# DDR_Memory.net
KiCad netlist of a schematic drawn in Altium Designer
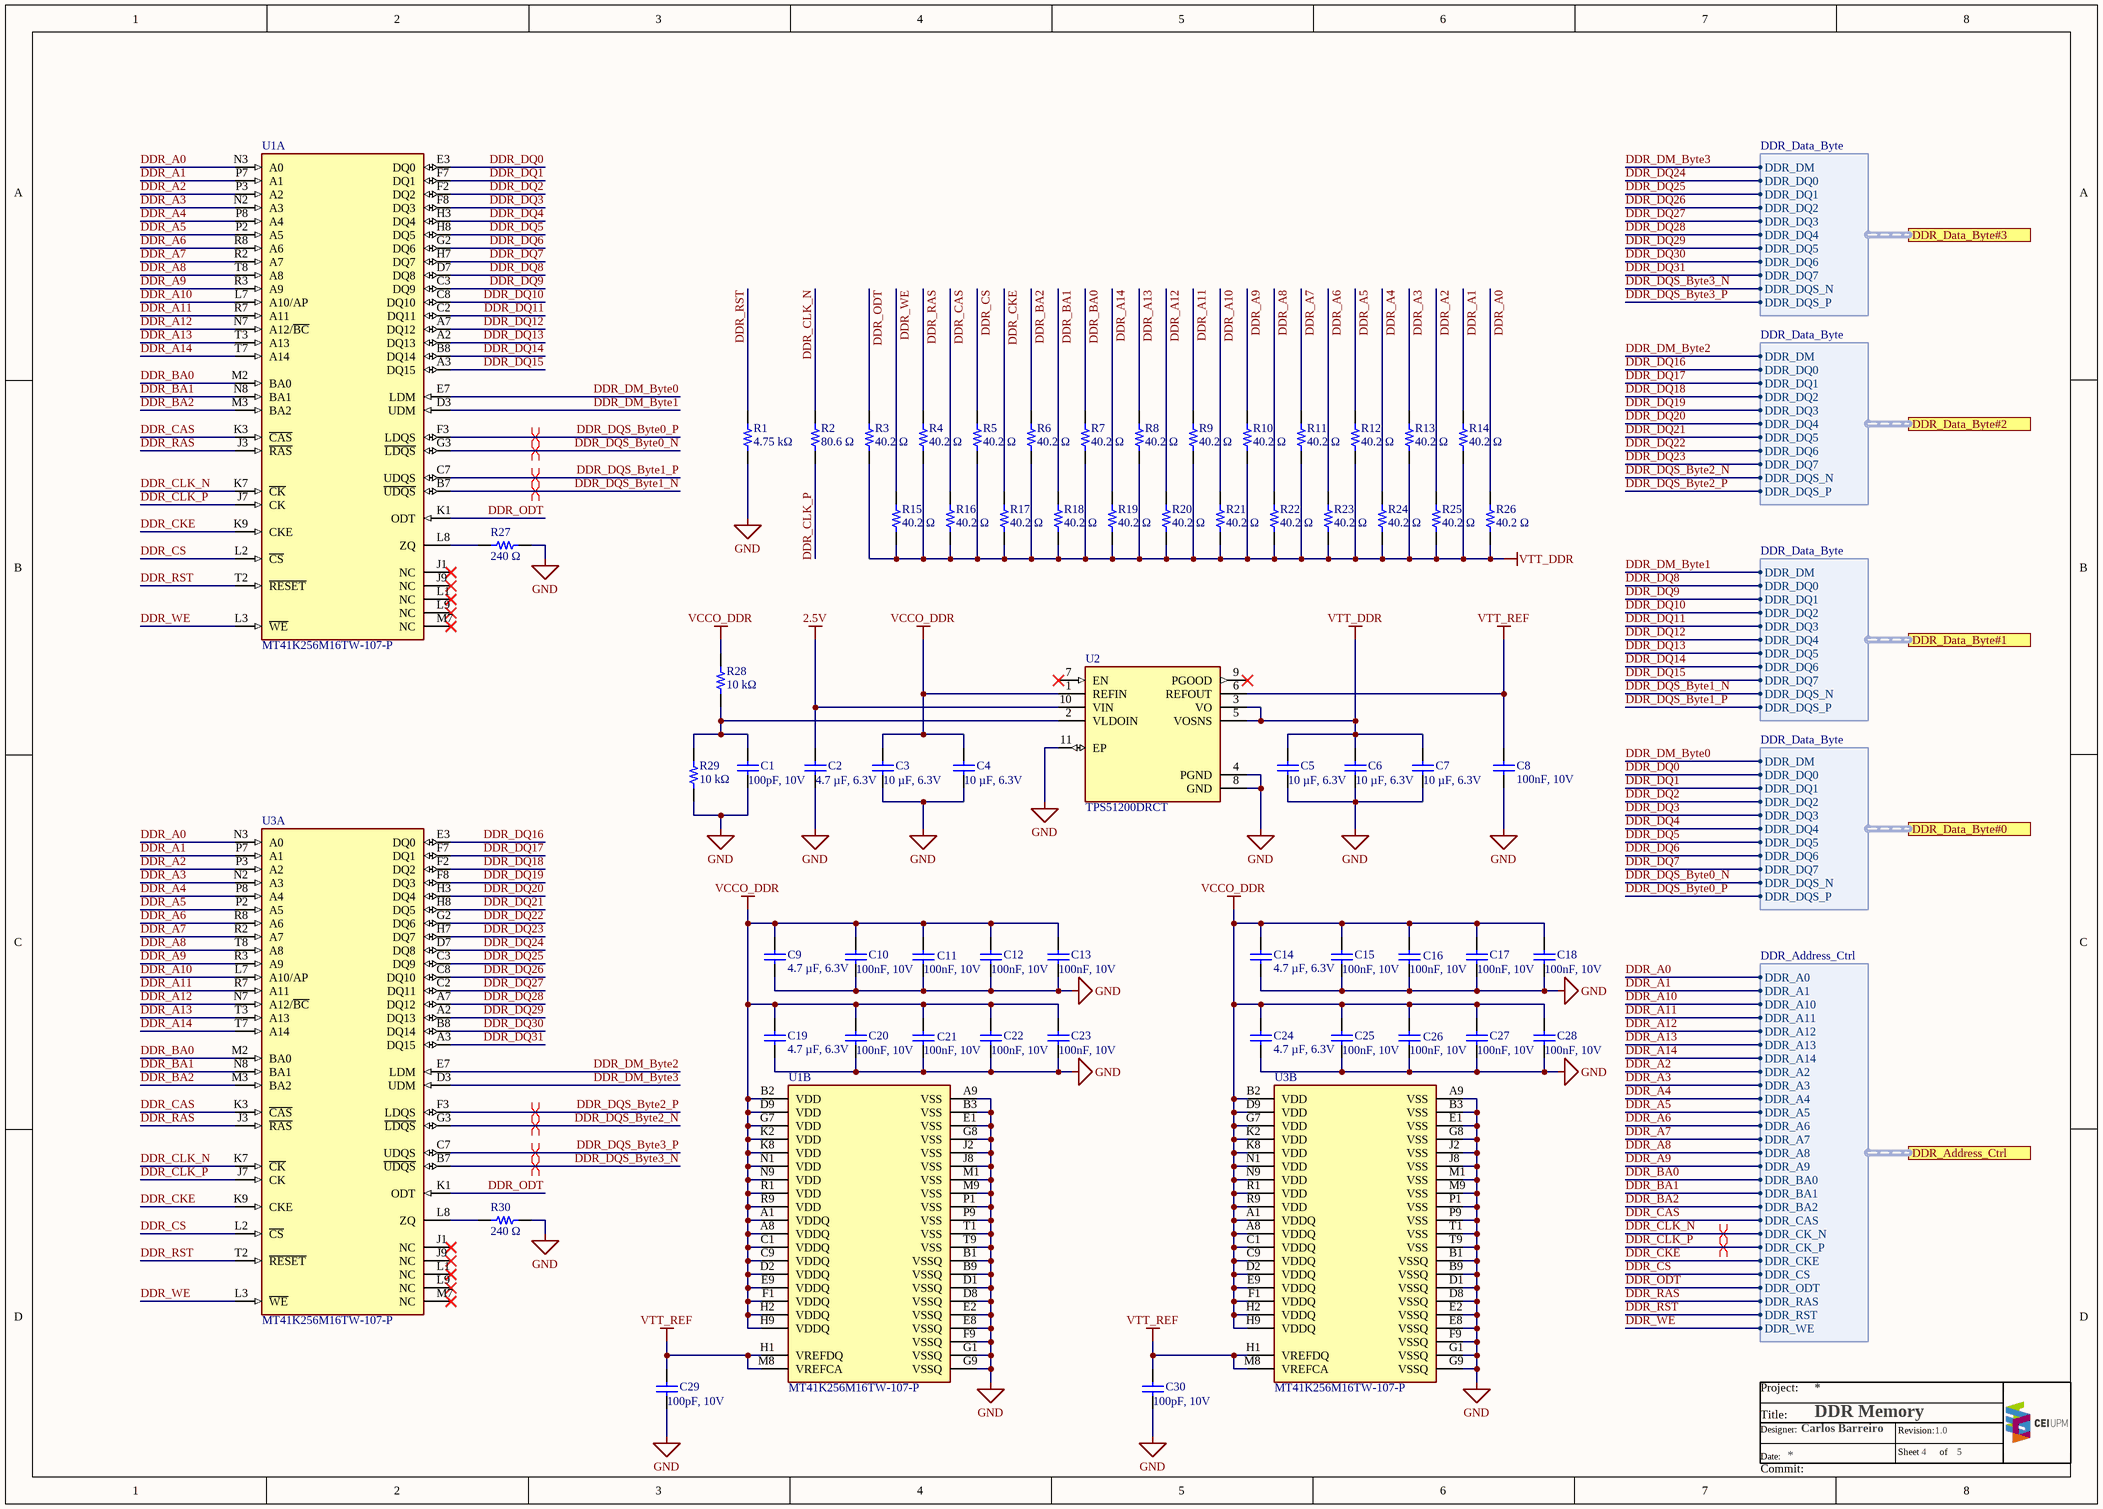
[diagram p0: DDR_Memory.SchDoc]

(export (version "E")
  (design (tool "Eeschema 10.0.6"))
  (components
    (comp (ref "C1")
      (value "100pF, 10V")
      (footprint "WURTH_WCAP-CSGP_0402")
      (description "WCAP-CSGP Multilayer Ceramic Chip Capacitor, General Purpose, size 0402, NP0, 100pF, 10V")
      (fields
        (field (name "MANUFACTURER PART NUMBER") "885012005013")
        (field (name "MANUFACTURER") "Wurth Elektronik")
      )
      (libsource (lib "SpaceVNXBaseBoard") (part "885012005013"))
    )
    (comp (ref "C2")
      (value "4.7 µF, 6.3V")
      (footprint "WURTH_WCAP-CSGP_0402")
      (description "Multilayer Ceramic Capacitors MLCC, size 0402, X5R, 4.7 µF, 6.3V")
      (fields
        (field (name "MANUFACTURER PART NUMBER") "GRM155C80J475MEAAD")
        (field (name "MANUFACTURER") "Murata")
      )
      (libsource (lib "SpaceVNXBaseBoard") (part "GRM155C80J475MEAAD"))
    )
    (comp (ref "C3")
      (value "10 µF, 6.3V")
      (footprint "WURTH_WCAP-CSGP_0402")
      (description "WCAP-CSGP Multilayer Ceramic Chip Capacitor, General Purpose, size 0402, X5R, 10uF, 6.3V")
      (fields
        (field (name "MANUFACTURER PART NUMBER") "885012105020")
        (field (name "MANUFACTURER") "Wurth Elektronik")
      )
      (libsource (lib "SpaceVNXBaseBoard") (part "885012105020"))
    )
    (comp (ref "C4")
      (value "10 µF, 6.3V")
      (footprint "WURTH_WCAP-CSGP_0402")
      (description "WCAP-CSGP Multilayer Ceramic Chip Capacitor, General Purpose, size 0402, X5R, 10uF, 6.3V")
      (fields
        (field (name "MANUFACTURER PART NUMBER") "885012105020")
        (field (name "MANUFACTURER") "Wurth Elektronik")
      )
      (libsource (lib "SpaceVNXBaseBoard") (part "885012105020"))
    )
    (comp (ref "C5")
      (value "10 µF, 6.3V")
      (footprint "WURTH_WCAP-CSGP_0402")
      (description "WCAP-CSGP Multilayer Ceramic Chip Capacitor, General Purpose, size 0402, X5R, 10uF, 6.3V")
      (fields
        (field (name "MANUFACTURER PART NUMBER") "885012105020")
        (field (name "MANUFACTURER") "Wurth Elektronik")
      )
      (libsource (lib "SpaceVNXBaseBoard") (part "885012105020"))
    )
    (comp (ref "C6")
      (value "10 µF, 6.3V")
      (footprint "WURTH_WCAP-CSGP_0402")
      (description "WCAP-CSGP Multilayer Ceramic Chip Capacitor, General Purpose, size 0402, X5R, 10uF, 6.3V")
      (fields
        (field (name "MANUFACTURER PART NUMBER") "885012105020")
        (field (name "MANUFACTURER") "Wurth Elektronik")
      )
      (libsource (lib "SpaceVNXBaseBoard") (part "885012105020"))
    )
    (comp (ref "C7")
      (value "10 µF, 6.3V")
      (footprint "WURTH_WCAP-CSGP_0402")
      (description "WCAP-CSGP Multilayer Ceramic Chip Capacitor, General Purpose, size 0402, X5R, 10uF, 6.3V")
      (fields
        (field (name "MANUFACTURER PART NUMBER") "885012105020")
        (field (name "MANUFACTURER") "Wurth Elektronik")
      )
      (libsource (lib "SpaceVNXBaseBoard") (part "885012105020"))
    )
    (comp (ref "C8")
      (value "100nF, 10V")
      (footprint "WURTH_WCAP-CSGP_0402")
      (description "WCAP-CSGP Multilayer Ceramic Chip Capacitor, General Purpose, size 0402, X7R, 100nF, 10V")
      (fields
        (field (name "MANUFACTURER PART NUMBER") "885012205018")
        (field (name "MANUFACTURER") "Wurth Elektronik")
      )
      (libsource (lib "SpaceVNXBaseBoard") (part "885012205018"))
    )
    (comp (ref "C9")
      (value "4.7 µF, 6.3V")
      (footprint "WURTH_WCAP-CSGP_0402")
      (description "Multilayer Ceramic Capacitors MLCC, size 0402, X5R, 4.7 µF, 6.3V")
      (fields
        (field (name "MANUFACTURER PART NUMBER") "GRM155C80J475MEAAD")
        (field (name "MANUFACTURER") "Murata")
      )
      (libsource (lib "SpaceVNXBaseBoard") (part "GRM155C80J475MEAAD"))
    )
    (comp (ref "C10")
      (value "100nF, 10V")
      (footprint "WURTH_WCAP-CSGP_0402")
      (description "WCAP-CSGP Multilayer Ceramic Chip Capacitor, General Purpose, size 0402, X7R, 100nF, 10V")
      (fields
        (field (name "MANUFACTURER PART NUMBER") "885012205018")
        (field (name "MANUFACTURER") "Wurth Elektronik")
      )
      (libsource (lib "SpaceVNXBaseBoard") (part "885012205018"))
    )
    (comp (ref "C11")
      (value "100nF, 10V")
      (footprint "WURTH_WCAP-CSGP_0402")
      (description "WCAP-CSGP Multilayer Ceramic Chip Capacitor, General Purpose, size 0402, X7R, 100nF, 10V")
      (fields
        (field (name "MANUFACTURER PART NUMBER") "885012205018")
        (field (name "MANUFACTURER") "Wurth Elektronik")
      )
      (libsource (lib "SpaceVNXBaseBoard") (part "885012205018"))
    )
    (comp (ref "C12")
      (value "100nF, 10V")
      (footprint "WURTH_WCAP-CSGP_0402")
      (description "WCAP-CSGP Multilayer Ceramic Chip Capacitor, General Purpose, size 0402, X7R, 100nF, 10V")
      (fields
        (field (name "MANUFACTURER PART NUMBER") "885012205018")
        (field (name "MANUFACTURER") "Wurth Elektronik")
      )
      (libsource (lib "SpaceVNXBaseBoard") (part "885012205018"))
    )
    (comp (ref "C13")
      (value "100nF, 10V")
      (footprint "WURTH_WCAP-CSGP_0402")
      (description "WCAP-CSGP Multilayer Ceramic Chip Capacitor, General Purpose, size 0402, X7R, 100nF, 10V")
      (fields
        (field (name "MANUFACTURER PART NUMBER") "885012205018")
        (field (name "MANUFACTURER") "Wurth Elektronik")
      )
      (libsource (lib "SpaceVNXBaseBoard") (part "885012205018"))
    )
    (comp (ref "C14")
      (value "4.7 µF, 6.3V")
      (footprint "WURTH_WCAP-CSGP_0402")
      (description "Multilayer Ceramic Capacitors MLCC, size 0402, X5R, 4.7 µF, 6.3V")
      (fields
        (field (name "MANUFACTURER PART NUMBER") "GRM155C80J475MEAAD")
        (field (name "MANUFACTURER") "Murata")
      )
      (libsource (lib "SpaceVNXBaseBoard") (part "GRM155C80J475MEAAD"))
    )
    (comp (ref "C15")
      (value "100nF, 10V")
      (footprint "WURTH_WCAP-CSGP_0402")
      (description "WCAP-CSGP Multilayer Ceramic Chip Capacitor, General Purpose, size 0402, X7R, 100nF, 10V")
      (fields
        (field (name "MANUFACTURER PART NUMBER") "885012205018")
        (field (name "MANUFACTURER") "Wurth Elektronik")
      )
      (libsource (lib "SpaceVNXBaseBoard") (part "885012205018"))
    )
    (comp (ref "C16")
      (value "100nF, 10V")
      (footprint "WURTH_WCAP-CSGP_0402")
      (description "WCAP-CSGP Multilayer Ceramic Chip Capacitor, General Purpose, size 0402, X7R, 100nF, 10V")
      (fields
        (field (name "MANUFACTURER PART NUMBER") "885012205018")
        (field (name "MANUFACTURER") "Wurth Elektronik")
      )
      (libsource (lib "SpaceVNXBaseBoard") (part "885012205018"))
    )
    (comp (ref "C17")
      (value "100nF, 10V")
      (footprint "WURTH_WCAP-CSGP_0402")
      (description "WCAP-CSGP Multilayer Ceramic Chip Capacitor, General Purpose, size 0402, X7R, 100nF, 10V")
      (fields
        (field (name "MANUFACTURER PART NUMBER") "885012205018")
        (field (name "MANUFACTURER") "Wurth Elektronik")
      )
      (libsource (lib "SpaceVNXBaseBoard") (part "885012205018"))
    )
    (comp (ref "C18")
      (value "100nF, 10V")
      (footprint "WURTH_WCAP-CSGP_0402")
      (description "WCAP-CSGP Multilayer Ceramic Chip Capacitor, General Purpose, size 0402, X7R, 100nF, 10V")
      (fields
        (field (name "MANUFACTURER PART NUMBER") "885012205018")
        (field (name "MANUFACTURER") "Wurth Elektronik")
      )
      (libsource (lib "SpaceVNXBaseBoard") (part "885012205018"))
    )
    (comp (ref "C19")
      (value "4.7 µF, 6.3V")
      (footprint "WURTH_WCAP-CSGP_0402")
      (description "Multilayer Ceramic Capacitors MLCC, size 0402, X5R, 4.7 µF, 6.3V")
      (fields
        (field (name "MANUFACTURER PART NUMBER") "GRM155C80J475MEAAD")
        (field (name "MANUFACTURER") "Murata")
      )
      (libsource (lib "SpaceVNXBaseBoard") (part "GRM155C80J475MEAAD"))
    )
    (comp (ref "C20")
      (value "100nF, 10V")
      (footprint "WURTH_WCAP-CSGP_0402")
      (description "WCAP-CSGP Multilayer Ceramic Chip Capacitor, General Purpose, size 0402, X7R, 100nF, 10V")
      (fields
        (field (name "MANUFACTURER PART NUMBER") "885012205018")
        (field (name "MANUFACTURER") "Wurth Elektronik")
      )
      (libsource (lib "SpaceVNXBaseBoard") (part "885012205018"))
    )
    (comp (ref "C21")
      (value "100nF, 10V")
      (footprint "WURTH_WCAP-CSGP_0402")
      (description "WCAP-CSGP Multilayer Ceramic Chip Capacitor, General Purpose, size 0402, X7R, 100nF, 10V")
      (fields
        (field (name "MANUFACTURER PART NUMBER") "885012205018")
        (field (name "MANUFACTURER") "Wurth Elektronik")
      )
      (libsource (lib "SpaceVNXBaseBoard") (part "885012205018"))
    )
    (comp (ref "C22")
      (value "100nF, 10V")
      (footprint "WURTH_WCAP-CSGP_0402")
      (description "WCAP-CSGP Multilayer Ceramic Chip Capacitor, General Purpose, size 0402, X7R, 100nF, 10V")
      (fields
        (field (name "MANUFACTURER PART NUMBER") "885012205018")
        (field (name "MANUFACTURER") "Wurth Elektronik")
      )
      (libsource (lib "SpaceVNXBaseBoard") (part "885012205018"))
    )
    (comp (ref "C23")
      (value "100nF, 10V")
      (footprint "WURTH_WCAP-CSGP_0402")
      (description "WCAP-CSGP Multilayer Ceramic Chip Capacitor, General Purpose, size 0402, X7R, 100nF, 10V")
      (fields
        (field (name "MANUFACTURER PART NUMBER") "885012205018")
        (field (name "MANUFACTURER") "Wurth Elektronik")
      )
      (libsource (lib "SpaceVNXBaseBoard") (part "885012205018"))
    )
    (comp (ref "C24")
      (value "4.7 µF, 6.3V")
      (footprint "WURTH_WCAP-CSGP_0402")
      (description "Multilayer Ceramic Capacitors MLCC, size 0402, X5R, 4.7 µF, 6.3V")
      (fields
        (field (name "MANUFACTURER PART NUMBER") "GRM155C80J475MEAAD")
        (field (name "MANUFACTURER") "Murata")
      )
      (libsource (lib "SpaceVNXBaseBoard") (part "GRM155C80J475MEAAD"))
    )
    (comp (ref "C25")
      (value "100nF, 10V")
      (footprint "WURTH_WCAP-CSGP_0402")
      (description "WCAP-CSGP Multilayer Ceramic Chip Capacitor, General Purpose, size 0402, X7R, 100nF, 10V")
      (fields
        (field (name "MANUFACTURER PART NUMBER") "885012205018")
        (field (name "MANUFACTURER") "Wurth Elektronik")
      )
      (libsource (lib "SpaceVNXBaseBoard") (part "885012205018"))
    )
    (comp (ref "C26")
      (value "100nF, 10V")
      (footprint "WURTH_WCAP-CSGP_0402")
      (description "WCAP-CSGP Multilayer Ceramic Chip Capacitor, General Purpose, size 0402, X7R, 100nF, 10V")
      (fields
        (field (name "MANUFACTURER PART NUMBER") "885012205018")
        (field (name "MANUFACTURER") "Wurth Elektronik")
      )
      (libsource (lib "SpaceVNXBaseBoard") (part "885012205018"))
    )
    (comp (ref "C27")
      (value "100nF, 10V")
      (footprint "WURTH_WCAP-CSGP_0402")
      (description "WCAP-CSGP Multilayer Ceramic Chip Capacitor, General Purpose, size 0402, X7R, 100nF, 10V")
      (fields
        (field (name "MANUFACTURER PART NUMBER") "885012205018")
        (field (name "MANUFACTURER") "Wurth Elektronik")
      )
      (libsource (lib "SpaceVNXBaseBoard") (part "885012205018"))
    )
    (comp (ref "C28")
      (value "100nF, 10V")
      (footprint "WURTH_WCAP-CSGP_0402")
      (description "WCAP-CSGP Multilayer Ceramic Chip Capacitor, General Purpose, size 0402, X7R, 100nF, 10V")
      (fields
        (field (name "MANUFACTURER PART NUMBER") "885012205018")
        (field (name "MANUFACTURER") "Wurth Elektronik")
      )
      (libsource (lib "SpaceVNXBaseBoard") (part "885012205018"))
    )
    (comp (ref "C29")
      (value "100pF, 10V")
      (footprint "WURTH_WCAP-CSGP_0402")
      (description "WCAP-CSGP Multilayer Ceramic Chip Capacitor, General Purpose, size 0402, NP0, 100pF, 10V")
      (fields
        (field (name "MANUFACTURER PART NUMBER") "885012005013")
        (field (name "MANUFACTURER") "Wurth Elektronik")
      )
      (libsource (lib "SpaceVNXBaseBoard") (part "885012005013"))
    )
    (comp (ref "C30")
      (value "100pF, 10V")
      (footprint "WURTH_WCAP-CSGP_0402")
      (description "WCAP-CSGP Multilayer Ceramic Chip Capacitor, General Purpose, size 0402, NP0, 100pF, 10V")
      (fields
        (field (name "MANUFACTURER PART NUMBER") "885012005013")
        (field (name "MANUFACTURER") "Wurth Elektronik")
      )
      (libsource (lib "SpaceVNXBaseBoard") (part "885012005013"))
    )
    (comp (ref "R1")
      (value "4.75 kΩ")
      (footprint "PANASONIC_ERJ2G_0402")
      (description "General Purpose Thick Film Chip Resistors")
      (fields (field (name "MANUFACTURER") "Panasonic"))
      (libsource (lib "SpaceVNXBaseBoard") (part "ERJ2RKF4751X"))
    )
    (comp (ref "R2")
      (value "80.6 Ω")
      (footprint "PANASONIC_ERJ2G_0402")
      (description "General Purpose Thick Film Chip Resistors")
      (fields (field (name "MANUFACTURER") "Panasonic"))
      (libsource (lib "SpaceVNXBaseBoard") (part "ERJ2RKF80R6X"))
    )
    (comp (ref "R3")
      (value "40.2 Ω")
      (footprint "PANASONIC_ERJ2G_0402")
      (description "General Purpose Thick Film Chip Resistors")
      (fields (field (name "MANUFACTURER") "Panasonic"))
      (libsource (lib "SpaceVNXBaseBoard") (part "ERJ2RKF40R2X"))
    )
    (comp (ref "R4")
      (value "40.2 Ω")
      (footprint "PANASONIC_ERJ2G_0402")
      (description "General Purpose Thick Film Chip Resistors")
      (fields (field (name "MANUFACTURER") "Panasonic"))
      (libsource (lib "SpaceVNXBaseBoard") (part "ERJ2RKF40R2X"))
    )
    (comp (ref "R5")
      (value "40.2 Ω")
      (footprint "PANASONIC_ERJ2G_0402")
      (description "General Purpose Thick Film Chip Resistors")
      (fields (field (name "MANUFACTURER") "Panasonic"))
      (libsource (lib "SpaceVNXBaseBoard") (part "ERJ2RKF40R2X"))
    )
    (comp (ref "R6")
      (value "40.2 Ω")
      (footprint "PANASONIC_ERJ2G_0402")
      (description "General Purpose Thick Film Chip Resistors")
      (fields (field (name "MANUFACTURER") "Panasonic"))
      (libsource (lib "SpaceVNXBaseBoard") (part "ERJ2RKF40R2X"))
    )
    (comp (ref "R7")
      (value "40.2 Ω")
      (footprint "PANASONIC_ERJ2G_0402")
      (description "General Purpose Thick Film Chip Resistors")
      (fields (field (name "MANUFACTURER") "Panasonic"))
      (libsource (lib "SpaceVNXBaseBoard") (part "ERJ2RKF40R2X"))
    )
    (comp (ref "R8")
      (value "40.2 Ω")
      (footprint "PANASONIC_ERJ2G_0402")
      (description "General Purpose Thick Film Chip Resistors")
      (fields (field (name "MANUFACTURER") "Panasonic"))
      (libsource (lib "SpaceVNXBaseBoard") (part "ERJ2RKF40R2X"))
    )
    (comp (ref "R9")
      (value "40.2 Ω")
      (footprint "PANASONIC_ERJ2G_0402")
      (description "General Purpose Thick Film Chip Resistors")
      (fields (field (name "MANUFACTURER") "Panasonic"))
      (libsource (lib "SpaceVNXBaseBoard") (part "ERJ2RKF40R2X"))
    )
    (comp (ref "R10")
      (value "40.2 Ω")
      (footprint "PANASONIC_ERJ2G_0402")
      (description "General Purpose Thick Film Chip Resistors")
      (fields (field (name "MANUFACTURER") "Panasonic"))
      (libsource (lib "SpaceVNXBaseBoard") (part "ERJ2RKF40R2X"))
    )
    (comp (ref "R11")
      (value "40.2 Ω")
      (footprint "PANASONIC_ERJ2G_0402")
      (description "General Purpose Thick Film Chip Resistors")
      (fields (field (name "MANUFACTURER") "Panasonic"))
      (libsource (lib "SpaceVNXBaseBoard") (part "ERJ2RKF40R2X"))
    )
    (comp (ref "R12")
      (value "40.2 Ω")
      (footprint "PANASONIC_ERJ2G_0402")
      (description "General Purpose Thick Film Chip Resistors")
      (fields (field (name "MANUFACTURER") "Panasonic"))
      (libsource (lib "SpaceVNXBaseBoard") (part "ERJ2RKF40R2X"))
    )
    (comp (ref "R13")
      (value "40.2 Ω")
      (footprint "PANASONIC_ERJ2G_0402")
      (description "General Purpose Thick Film Chip Resistors")
      (fields (field (name "MANUFACTURER") "Panasonic"))
      (libsource (lib "SpaceVNXBaseBoard") (part "ERJ2RKF40R2X"))
    )
    (comp (ref "R14")
      (value "40.2 Ω")
      (footprint "PANASONIC_ERJ2G_0402")
      (description "General Purpose Thick Film Chip Resistors")
      (fields (field (name "MANUFACTURER") "Panasonic"))
      (libsource (lib "SpaceVNXBaseBoard") (part "ERJ2RKF40R2X"))
    )
    (comp (ref "R15")
      (value "40.2 Ω")
      (footprint "PANASONIC_ERJ2G_0402")
      (description "General Purpose Thick Film Chip Resistors")
      (fields (field (name "MANUFACTURER") "Panasonic"))
      (libsource (lib "SpaceVNXBaseBoard") (part "ERJ2RKF40R2X"))
    )
    (comp (ref "R16")
      (value "40.2 Ω")
      (footprint "PANASONIC_ERJ2G_0402")
      (description "General Purpose Thick Film Chip Resistors")
      (fields (field (name "MANUFACTURER") "Panasonic"))
      (libsource (lib "SpaceVNXBaseBoard") (part "ERJ2RKF40R2X"))
    )
    (comp (ref "R17")
      (value "40.2 Ω")
      (footprint "PANASONIC_ERJ2G_0402")
      (description "General Purpose Thick Film Chip Resistors")
      (fields (field (name "MANUFACTURER") "Panasonic"))
      (libsource (lib "SpaceVNXBaseBoard") (part "ERJ2RKF40R2X"))
    )
    (comp (ref "R18")
      (value "40.2 Ω")
      (footprint "PANASONIC_ERJ2G_0402")
      (description "General Purpose Thick Film Chip Resistors")
      (fields (field (name "MANUFACTURER") "Panasonic"))
      (libsource (lib "SpaceVNXBaseBoard") (part "ERJ2RKF40R2X"))
    )
    (comp (ref "R19")
      (value "40.2 Ω")
      (footprint "PANASONIC_ERJ2G_0402")
      (description "General Purpose Thick Film Chip Resistors")
      (fields (field (name "MANUFACTURER") "Panasonic"))
      (libsource (lib "SpaceVNXBaseBoard") (part "ERJ2RKF40R2X"))
    )
    (comp (ref "R20")
      (value "40.2 Ω")
      (footprint "PANASONIC_ERJ2G_0402")
      (description "General Purpose Thick Film Chip Resistors")
      (fields (field (name "MANUFACTURER") "Panasonic"))
      (libsource (lib "SpaceVNXBaseBoard") (part "ERJ2RKF40R2X"))
    )
    (comp (ref "R21")
      (value "40.2 Ω")
      (footprint "PANASONIC_ERJ2G_0402")
      (description "General Purpose Thick Film Chip Resistors")
      (fields (field (name "MANUFACTURER") "Panasonic"))
      (libsource (lib "SpaceVNXBaseBoard") (part "ERJ2RKF40R2X"))
    )
    (comp (ref "R22")
      (value "40.2 Ω")
      (footprint "PANASONIC_ERJ2G_0402")
      (description "General Purpose Thick Film Chip Resistors")
      (fields (field (name "MANUFACTURER") "Panasonic"))
      (libsource (lib "SpaceVNXBaseBoard") (part "ERJ2RKF40R2X"))
    )
    (comp (ref "R23")
      (value "40.2 Ω")
      (footprint "PANASONIC_ERJ2G_0402")
      (description "General Purpose Thick Film Chip Resistors")
      (fields (field (name "MANUFACTURER") "Panasonic"))
      (libsource (lib "SpaceVNXBaseBoard") (part "ERJ2RKF40R2X"))
    )
    (comp (ref "R24")
      (value "40.2 Ω")
      (footprint "PANASONIC_ERJ2G_0402")
      (description "General Purpose Thick Film Chip Resistors")
      (fields (field (name "MANUFACTURER") "Panasonic"))
      (libsource (lib "SpaceVNXBaseBoard") (part "ERJ2RKF40R2X"))
    )
    (comp (ref "R25")
      (value "40.2 Ω")
      (footprint "PANASONIC_ERJ2G_0402")
      (description "General Purpose Thick Film Chip Resistors")
      (fields (field (name "MANUFACTURER") "Panasonic"))
      (libsource (lib "SpaceVNXBaseBoard") (part "ERJ2RKF40R2X"))
    )
    (comp (ref "R26")
      (value "40.2 Ω")
      (footprint "PANASONIC_ERJ2G_0402")
      (description "General Purpose Thick Film Chip Resistors")
      (fields (field (name "MANUFACTURER") "Panasonic"))
      (libsource (lib "SpaceVNXBaseBoard") (part "ERJ2RKF40R2X"))
    )
    (comp (ref "R27")
      (value "240 Ω")
      (footprint "PANASONIC_ERJ2G_0402")
      (description "General Purpose Thick Film Chip Resistors")
      (fields (field (name "MANUFACTURER") "Panasonic"))
      (libsource (lib "SpaceVNXBaseBoard") (part "ERJ2GEJ241X"))
    )
    (comp (ref "R28")
      (value "10 kΩ")
      (footprint "PANASONIC_ERJ2G_0402")
      (description "General Purpose Thick Film Chip Resistors")
      (fields (field (name "MANUFACTURER") "Panasonic"))
      (libsource (lib "SpaceVNXBaseBoard") (part "ERJ2RKF1002X"))
    )
    (comp (ref "R29")
      (value "10 kΩ")
      (footprint "PANASONIC_ERJ2G_0402")
      (description "General Purpose Thick Film Chip Resistors")
      (fields (field (name "MANUFACTURER") "Panasonic"))
      (libsource (lib "SpaceVNXBaseBoard") (part "ERJ2RKF1002X"))
    )
    (comp (ref "R30")
      (value "240 Ω")
      (footprint "PANASONIC_ERJ2G_0402")
      (description "General Purpose Thick Film Chip Resistors")
      (fields (field (name "MANUFACTURER") "Panasonic"))
      (libsource (lib "SpaceVNXBaseBoard") (part "ERJ2GEJ241X"))
    )
    (comp (ref "U1")
      (value "MT41K256M16TW-107-P")
      (footprint "Micron_TW")
      (description "DDR3L SRAM 256Mb*16")
      (libsource (lib "SpaceVNXBaseBoard") (part "MT41K256M16TW-107-P"))
    )
    (comp (ref "U2")
      (value "TPS51200DRCT")
      (footprint "TEXAS_VSON10")
      (fields (field (name "MF") "Texas Instruments"))
      (libsource (lib "SpaceVNXBaseBoard") (part "TPS51200DRCT"))
    )
    (comp (ref "U3")
      (value "MT41K256M16TW-107-P")
      (footprint "Micron_TW")
      (description "DDR3L SRAM 256Mb*16")
      (libsource (lib "SpaceVNXBaseBoard") (part "MT41K256M16TW-107-P"))
    )
  )
  (nets
    (net (code "3") (name "/DDR_A0") (class "Default")
      (node (ref "R26") (pin "1") (pinfunction "1_1") (pintype "passive"))
      (node (ref "U1") (pin "N3") (pinfunction "A0_N3") (pintype "input"))
      (node (ref "U3") (pin "N3") (pinfunction "A0_N3") (pintype "input"))
    )
    (net (code "4") (name "/DDR_A1") (class "Default")
      (node (ref "R14") (pin "1") (pinfunction "1_1") (pintype "passive"))
      (node (ref "U1") (pin "P7") (pinfunction "A1_P7") (pintype "input"))
      (node (ref "U3") (pin "P7") (pinfunction "A1_P7") (pintype "input"))
    )
    (net (code "5") (name "/DDR_A2") (class "Default")
      (node (ref "R25") (pin "1") (pinfunction "1_1") (pintype "passive"))
      (node (ref "U1") (pin "P3") (pinfunction "A2_P3") (pintype "input"))
      (node (ref "U3") (pin "P3") (pinfunction "A2_P3") (pintype "input"))
    )
    (net (code "6") (name "/DDR_A3") (class "Default")
      (node (ref "R13") (pin "1") (pinfunction "1_1") (pintype "passive"))
      (node (ref "U1") (pin "N2") (pinfunction "A3_N2") (pintype "input"))
      (node (ref "U3") (pin "N2") (pinfunction "A3_N2") (pintype "input"))
    )
    (net (code "7") (name "/DDR_A4") (class "Default")
      (node (ref "R24") (pin "1") (pinfunction "1_1") (pintype "passive"))
      (node (ref "U1") (pin "P8") (pinfunction "A4_P8") (pintype "input"))
      (node (ref "U3") (pin "P8") (pinfunction "A4_P8") (pintype "input"))
    )
    (net (code "8") (name "/DDR_A5") (class "Default")
      (node (ref "R12") (pin "1") (pinfunction "1_1") (pintype "passive"))
      (node (ref "U1") (pin "P2") (pinfunction "A5_P2") (pintype "input"))
      (node (ref "U3") (pin "P2") (pinfunction "A5_P2") (pintype "input"))
    )
    (net (code "9") (name "/DDR_A6") (class "Default")
      (node (ref "R23") (pin "1") (pinfunction "1_1") (pintype "passive"))
      (node (ref "U1") (pin "R8") (pinfunction "A6_R8") (pintype "input"))
      (node (ref "U3") (pin "R8") (pinfunction "A6_R8") (pintype "input"))
    )
    (net (code "10") (name "/DDR_A7") (class "Default")
      (node (ref "R11") (pin "1") (pinfunction "1_1") (pintype "passive"))
      (node (ref "U1") (pin "R2") (pinfunction "A7_R2") (pintype "input"))
      (node (ref "U3") (pin "R2") (pinfunction "A7_R2") (pintype "input"))
    )
    (net (code "11") (name "/DDR_A8") (class "Default")
      (node (ref "R22") (pin "1") (pinfunction "1_1") (pintype "passive"))
      (node (ref "U1") (pin "T8") (pinfunction "A8_T8") (pintype "input"))
      (node (ref "U3") (pin "T8") (pinfunction "A8_T8") (pintype "input"))
    )
    (net (code "12") (name "/DDR_A9") (class "Default")
      (node (ref "R10") (pin "1") (pinfunction "1_1") (pintype "passive"))
      (node (ref "U1") (pin "R3") (pinfunction "A9_R3") (pintype "input"))
      (node (ref "U3") (pin "R3") (pinfunction "A9_R3") (pintype "input"))
    )
    (net (code "13") (name "/DDR_A10") (class "Default")
      (node (ref "R21") (pin "1") (pinfunction "1_1") (pintype "passive"))
      (node (ref "U1") (pin "L7") (pinfunction "A10/AP_L7") (pintype "input"))
      (node (ref "U3") (pin "L7") (pinfunction "A10/AP_L7") (pintype "input"))
    )
    (net (code "14") (name "/DDR_A11") (class "Default")
      (node (ref "R9") (pin "1") (pinfunction "1_1") (pintype "passive"))
      (node (ref "U1") (pin "R7") (pinfunction "A11_R7") (pintype "input"))
      (node (ref "U3") (pin "R7") (pinfunction "A11_R7") (pintype "input"))
    )
    (net (code "15") (name "/DDR_A12") (class "Default")
      (node (ref "R20") (pin "1") (pinfunction "1_1") (pintype "passive"))
      (node (ref "U1") (pin "N7") (pinfunction "A12/~{BC}_N7") (pintype "input"))
      (node (ref "U3") (pin "N7") (pinfunction "A12/~{BC}_N7") (pintype "input"))
    )
    (net (code "16") (name "/DDR_A13") (class "Default")
      (node (ref "R8") (pin "1") (pinfunction "1_1") (pintype "passive"))
      (node (ref "U1") (pin "T3") (pinfunction "A13_T3") (pintype "input"))
      (node (ref "U3") (pin "T3") (pinfunction "A13_T3") (pintype "input"))
    )
    (net (code "17") (name "/DDR_A14") (class "Default")
      (node (ref "R19") (pin "1") (pinfunction "1_1") (pintype "passive"))
      (node (ref "U1") (pin "T7") (pinfunction "A14_T7") (pintype "input"))
      (node (ref "U3") (pin "T7") (pinfunction "A14_T7") (pintype "input"))
    )
    (net (code "18") (name "/DDR_BA0") (class "Default")
      (node (ref "R7") (pin "1") (pinfunction "1_1") (pintype "passive"))
      (node (ref "U1") (pin "M2") (pinfunction "BA0_M2") (pintype "input"))
      (node (ref "U3") (pin "M2") (pinfunction "BA0_M2") (pintype "input"))
    )
    (net (code "19") (name "/DDR_BA1") (class "Default")
      (node (ref "R18") (pin "1") (pinfunction "1_1") (pintype "passive"))
      (node (ref "U1") (pin "N8") (pinfunction "BA1_N8") (pintype "input"))
      (node (ref "U3") (pin "N8") (pinfunction "BA1_N8") (pintype "input"))
    )
    (net (code "20") (name "/DDR_BA2") (class "Default")
      (node (ref "R6") (pin "1") (pinfunction "1_1") (pintype "passive"))
      (node (ref "U1") (pin "M3") (pinfunction "BA2_M3") (pintype "input"))
      (node (ref "U3") (pin "M3") (pinfunction "BA2_M3") (pintype "input"))
    )
    (net (code "21") (name "/DDR_CAS") (class "Default")
      (node (ref "R16") (pin "1") (pinfunction "1_1") (pintype "passive"))
      (node (ref "U1") (pin "K3") (pinfunction "~{CAS}_K3") (pintype "input"))
      (node (ref "U3") (pin "K3") (pinfunction "~{CAS}_K3") (pintype "input"))
    )
    (net (code "22") (name "/DDR_CKE") (class "Default")
      (node (ref "R17") (pin "1") (pinfunction "1_1") (pintype "passive"))
      (node (ref "U1") (pin "K9") (pinfunction "CKE_K9") (pintype "input"))
      (node (ref "U3") (pin "K9") (pinfunction "CKE_K9") (pintype "input"))
    )
    (net (code "23") (name "/DDR_CLK_N") (class "Default")
      (node (ref "R2") (pin "2") (pinfunction "2_2") (pintype "passive"))
      (node (ref "U1") (pin "K7") (pinfunction "~{CK}_K7") (pintype "input"))
      (node (ref "U3") (pin "K7") (pinfunction "~{CK}_K7") (pintype "input"))
    )
    (net (code "24") (name "/DDR_CLK_P") (class "Default")
      (node (ref "R2") (pin "1") (pinfunction "1_1") (pintype "passive"))
      (node (ref "U1") (pin "J7") (pinfunction "CK_J7") (pintype "input"))
      (node (ref "U3") (pin "J7") (pinfunction "CK_J7") (pintype "input"))
    )
    (net (code "25") (name "/DDR_CS") (class "Default")
      (node (ref "R5") (pin "1") (pinfunction "1_1") (pintype "passive"))
      (node (ref "U1") (pin "L2") (pinfunction "~{CS}_L2") (pintype "input"))
      (node (ref "U3") (pin "L2") (pinfunction "~{CS}_L2") (pintype "input"))
    )
    (net (code "26") (name "/DDR_DM_Byte0") (class "Default")
      (node (ref "U1") (pin "E7") (pinfunction "LDM_E7") (pintype "input"))
    )
    (net (code "27") (name "/DDR_DM_Byte1") (class "Default")
      (node (ref "U1") (pin "D3") (pinfunction "UDM_D3") (pintype "input"))
    )
    (net (code "28") (name "/DDR_DM_Byte2") (class "Default")
      (node (ref "U3") (pin "E7") (pinfunction "LDM_E7") (pintype "input"))
    )
    (net (code "29") (name "/DDR_DM_Byte3") (class "Default")
      (node (ref "U3") (pin "D3") (pinfunction "UDM_D3") (pintype "input"))
    )
    (net (code "30") (name "/DDR_DQ0") (class "Default")
      (node (ref "U1") (pin "E3") (pinfunction "DQ0_E3") (pintype "bidirectional"))
    )
    (net (code "31") (name "/DDR_DQ1") (class "Default")
      (node (ref "U1") (pin "F7") (pinfunction "DQ1_F7") (pintype "bidirectional"))
    )
    (net (code "32") (name "/DDR_DQ2") (class "Default")
      (node (ref "U1") (pin "F2") (pinfunction "DQ2_F2") (pintype "bidirectional"))
    )
    (net (code "33") (name "/DDR_DQ3") (class "Default")
      (node (ref "U1") (pin "F8") (pinfunction "DQ3_F8") (pintype "bidirectional"))
    )
    (net (code "34") (name "/DDR_DQ4") (class "Default")
      (node (ref "U1") (pin "H3") (pinfunction "DQ4_H3") (pintype "bidirectional"))
    )
    (net (code "35") (name "/DDR_DQ5") (class "Default")
      (node (ref "U1") (pin "H8") (pinfunction "DQ5_H8") (pintype "bidirectional"))
    )
    (net (code "36") (name "/DDR_DQ6") (class "Default")
      (node (ref "U1") (pin "G2") (pinfunction "DQ6_G2") (pintype "bidirectional"))
    )
    (net (code "37") (name "/DDR_DQ7") (class "Default")
      (node (ref "U1") (pin "H7") (pinfunction "DQ7_H7") (pintype "bidirectional"))
    )
    (net (code "38") (name "/DDR_DQ8") (class "Default")
      (node (ref "U1") (pin "D7") (pinfunction "DQ8_D7") (pintype "bidirectional"))
    )
    (net (code "39") (name "/DDR_DQ9") (class "Default")
      (node (ref "U1") (pin "C3") (pinfunction "DQ9_C3") (pintype "bidirectional"))
    )
    (net (code "40") (name "/DDR_DQ10") (class "Default")
      (node (ref "U1") (pin "C8") (pinfunction "DQ10_C8") (pintype "bidirectional"))
    )
    (net (code "41") (name "/DDR_DQ11") (class "Default")
      (node (ref "U1") (pin "C2") (pinfunction "DQ11_C2") (pintype "bidirectional"))
    )
    (net (code "42") (name "/DDR_DQ12") (class "Default")
      (node (ref "U1") (pin "A7") (pinfunction "DQ12_A7") (pintype "bidirectional"))
    )
    (net (code "43") (name "/DDR_DQ13") (class "Default")
      (node (ref "U1") (pin "A2") (pinfunction "DQ13_A2") (pintype "bidirectional"))
    )
    (net (code "44") (name "/DDR_DQ14") (class "Default")
      (node (ref "U1") (pin "B8") (pinfunction "DQ14_B8") (pintype "bidirectional"))
    )
    (net (code "45") (name "/DDR_DQ15") (class "Default")
      (node (ref "U1") (pin "A3") (pinfunction "DQ15_A3") (pintype "bidirectional"))
    )
    (net (code "46") (name "/DDR_DQ16") (class "Default")
      (node (ref "U3") (pin "E3") (pinfunction "DQ0_E3") (pintype "bidirectional"))
    )
    (net (code "47") (name "/DDR_DQ17") (class "Default")
      (node (ref "U3") (pin "F7") (pinfunction "DQ1_F7") (pintype "bidirectional"))
    )
    (net (code "48") (name "/DDR_DQ18") (class "Default")
      (node (ref "U3") (pin "F2") (pinfunction "DQ2_F2") (pintype "bidirectional"))
    )
    (net (code "49") (name "/DDR_DQ19") (class "Default")
      (node (ref "U3") (pin "F8") (pinfunction "DQ3_F8") (pintype "bidirectional"))
    )
    (net (code "50") (name "/DDR_DQ20") (class "Default")
      (node (ref "U3") (pin "H3") (pinfunction "DQ4_H3") (pintype "bidirectional"))
    )
    (net (code "51") (name "/DDR_DQ21") (class "Default")
      (node (ref "U3") (pin "H8") (pinfunction "DQ5_H8") (pintype "bidirectional"))
    )
    (net (code "52") (name "/DDR_DQ22") (class "Default")
      (node (ref "U3") (pin "G2") (pinfunction "DQ6_G2") (pintype "bidirectional"))
    )
    (net (code "53") (name "/DDR_DQ23") (class "Default")
      (node (ref "U3") (pin "H7") (pinfunction "DQ7_H7") (pintype "bidirectional"))
    )
    (net (code "54") (name "/DDR_DQ24") (class "Default")
      (node (ref "U3") (pin "D7") (pinfunction "DQ8_D7") (pintype "bidirectional"))
    )
    (net (code "55") (name "/DDR_DQ25") (class "Default")
      (node (ref "U3") (pin "C3") (pinfunction "DQ9_C3") (pintype "bidirectional"))
    )
    (net (code "56") (name "/DDR_DQ26") (class "Default")
      (node (ref "U3") (pin "C8") (pinfunction "DQ10_C8") (pintype "bidirectional"))
    )
    (net (code "57") (name "/DDR_DQ27") (class "Default")
      (node (ref "U3") (pin "C2") (pinfunction "DQ11_C2") (pintype "bidirectional"))
    )
    (net (code "58") (name "/DDR_DQ28") (class "Default")
      (node (ref "U3") (pin "A7") (pinfunction "DQ12_A7") (pintype "bidirectional"))
    )
    (net (code "59") (name "/DDR_DQ29") (class "Default")
      (node (ref "U3") (pin "A2") (pinfunction "DQ13_A2") (pintype "bidirectional"))
    )
    (net (code "60") (name "/DDR_DQ30") (class "Default")
      (node (ref "U3") (pin "B8") (pinfunction "DQ14_B8") (pintype "bidirectional"))
    )
    (net (code "61") (name "/DDR_DQ31") (class "Default")
      (node (ref "U3") (pin "A3") (pinfunction "DQ15_A3") (pintype "bidirectional"))
    )
    (net (code "62") (name "/DDR_DQS_Byte0_N") (class "Default")
      (node (ref "U1") (pin "G3") (pinfunction "~{LDQS}_G3") (pintype "bidirectional"))
    )
    (net (code "63") (name "/DDR_DQS_Byte0_P") (class "Default")
      (node (ref "U1") (pin "F3") (pinfunction "LDQS_F3") (pintype "bidirectional"))
    )
    (net (code "64") (name "/DDR_DQS_Byte1_N") (class "Default")
      (node (ref "U1") (pin "B7") (pinfunction "~{UDQS}_B7") (pintype "bidirectional"))
    )
    (net (code "65") (name "/DDR_DQS_Byte1_P") (class "Default")
      (node (ref "U1") (pin "C7") (pinfunction "UDQS_C7") (pintype "bidirectional"))
    )
    (net (code "66") (name "/DDR_DQS_Byte2_N") (class "Default")
      (node (ref "U3") (pin "G3") (pinfunction "~{LDQS}_G3") (pintype "bidirectional"))
    )
    (net (code "67") (name "/DDR_DQS_Byte2_P") (class "Default")
      (node (ref "U3") (pin "F3") (pinfunction "LDQS_F3") (pintype "bidirectional"))
    )
    (net (code "68") (name "/DDR_DQS_Byte3_N") (class "Default")
      (node (ref "U3") (pin "B7") (pinfunction "~{UDQS}_B7") (pintype "bidirectional"))
    )
    (net (code "69") (name "/DDR_DQS_Byte3_P") (class "Default")
      (node (ref "U3") (pin "C7") (pinfunction "UDQS_C7") (pintype "bidirectional"))
    )
    (net (code "70") (name "/DDR_ODT") (class "Default")
      (node (ref "R3") (pin "1") (pinfunction "1_1") (pintype "passive"))
      (node (ref "U1") (pin "K1") (pinfunction "ODT_K1") (pintype "input"))
      (node (ref "U3") (pin "K1") (pinfunction "ODT_K1") (pintype "input"))
    )
    (net (code "71") (name "/DDR_RAS") (class "Default")
      (node (ref "R4") (pin "1") (pinfunction "1_1") (pintype "passive"))
      (node (ref "U1") (pin "J3") (pinfunction "~{RAS}_J3") (pintype "input"))
      (node (ref "U3") (pin "J3") (pinfunction "~{RAS}_J3") (pintype "input"))
    )
    (net (code "72") (name "/DDR_RST") (class "Default")
      (node (ref "R1") (pin "1") (pinfunction "1_1") (pintype "passive"))
      (node (ref "U1") (pin "T2") (pinfunction "~{RESET}_T2") (pintype "input"))
      (node (ref "U3") (pin "T2") (pinfunction "~{RESET}_T2") (pintype "input"))
    )
    (net (code "73") (name "/DDR_WE") (class "Default")
      (node (ref "R15") (pin "1") (pinfunction "1_1") (pintype "passive"))
      (node (ref "U1") (pin "L3") (pinfunction "~{WE}_L3") (pintype "input"))
      (node (ref "U3") (pin "L3") (pinfunction "~{WE}_L3") (pintype "input"))
    )
    (net (code "76") (name "2.5V") (class "Default")
      (node (ref "C2") (pin "2") (pinfunction "2_2") (pintype "passive"))
      (node (ref "U2") (pin "10") (pinfunction "VIN_10") (pintype "passive"))
    )
    (net (code "77") (name "GND") (class "Default")
      (node (ref "C1") (pin "1") (pinfunction "1_1") (pintype "passive"))
      (node (ref "C10") (pin "1") (pinfunction "1_1") (pintype "passive"))
      (node (ref "C11") (pin "1") (pinfunction "1_1") (pintype "passive"))
      (node (ref "C12") (pin "1") (pinfunction "1_1") (pintype "passive"))
      (node (ref "C13") (pin "1") (pinfunction "1_1") (pintype "passive"))
      (node (ref "C14") (pin "1") (pinfunction "1_1") (pintype "passive"))
      (node (ref "C15") (pin "1") (pinfunction "1_1") (pintype "passive"))
      (node (ref "C16") (pin "1") (pinfunction "1_1") (pintype "passive"))
      (node (ref "C17") (pin "1") (pinfunction "1_1") (pintype "passive"))
      (node (ref "C18") (pin "1") (pinfunction "1_1") (pintype "passive"))
      (node (ref "C19") (pin "1") (pinfunction "1_1") (pintype "passive"))
      (node (ref "C2") (pin "1") (pinfunction "1_1") (pintype "passive"))
      (node (ref "C20") (pin "1") (pinfunction "1_1") (pintype "passive"))
      (node (ref "C21") (pin "1") (pinfunction "1_1") (pintype "passive"))
      (node (ref "C22") (pin "1") (pinfunction "1_1") (pintype "passive"))
      (node (ref "C23") (pin "1") (pinfunction "1_1") (pintype "passive"))
      (node (ref "C24") (pin "1") (pinfunction "1_1") (pintype "passive"))
      (node (ref "C25") (pin "1") (pinfunction "1_1") (pintype "passive"))
      (node (ref "C26") (pin "1") (pinfunction "1_1") (pintype "passive"))
      (node (ref "C27") (pin "1") (pinfunction "1_1") (pintype "passive"))
      (node (ref "C28") (pin "1") (pinfunction "1_1") (pintype "passive"))
      (node (ref "C29") (pin "1") (pinfunction "1_1") (pintype "passive"))
      (node (ref "C3") (pin "1") (pinfunction "1_1") (pintype "passive"))
      (node (ref "C30") (pin "1") (pinfunction "1_1") (pintype "passive"))
      (node (ref "C4") (pin "1") (pinfunction "1_1") (pintype "passive"))
      (node (ref "C5") (pin "1") (pinfunction "1_1") (pintype "passive"))
      (node (ref "C6") (pin "1") (pinfunction "1_1") (pintype "passive"))
      (node (ref "C7") (pin "1") (pinfunction "1_1") (pintype "passive"))
      (node (ref "C8") (pin "1") (pinfunction "1_1") (pintype "passive"))
      (node (ref "C9") (pin "1") (pinfunction "1_1") (pintype "passive"))
      (node (ref "R1") (pin "2") (pinfunction "2_2") (pintype "passive"))
      (node (ref "R27") (pin "2") (pinfunction "2_2") (pintype "passive"))
      (node (ref "R29") (pin "1") (pinfunction "1_1") (pintype "passive"))
      (node (ref "R30") (pin "2") (pinfunction "2_2") (pintype "passive"))
      (node (ref "U1") (pin "A9") (pinfunction "VSS_A9") (pintype "power_in"))
      (node (ref "U1") (pin "B1") (pinfunction "VSSQ_B1") (pintype "power_in"))
      (node (ref "U1") (pin "B3") (pinfunction "VSS_B3") (pintype "power_in"))
      (node (ref "U1") (pin "B9") (pinfunction "VSSQ_B9") (pintype "power_in"))
      (node (ref "U1") (pin "D1") (pinfunction "VSSQ_D1") (pintype "power_in"))
      (node (ref "U1") (pin "D8") (pinfunction "VSSQ_D8") (pintype "power_in"))
      (node (ref "U1") (pin "E1") (pinfunction "VSS_E1") (pintype "power_in"))
      (node (ref "U1") (pin "E2") (pinfunction "VSSQ_E2") (pintype "power_in"))
      (node (ref "U1") (pin "E8") (pinfunction "VSSQ_E8") (pintype "power_in"))
      (node (ref "U1") (pin "F9") (pinfunction "VSSQ_F9") (pintype "power_in"))
      (node (ref "U1") (pin "G1") (pinfunction "VSSQ_G1") (pintype "power_in"))
      (node (ref "U1") (pin "G8") (pinfunction "VSS_G8") (pintype "power_in"))
      (node (ref "U1") (pin "G9") (pinfunction "VSSQ_G9") (pintype "power_in"))
      (node (ref "U1") (pin "J2") (pinfunction "VSS_J2") (pintype "power_in"))
      (node (ref "U1") (pin "J8") (pinfunction "VSS_J8") (pintype "power_in"))
      (node (ref "U1") (pin "M1") (pinfunction "VSS_M1") (pintype "power_in"))
      (node (ref "U1") (pin "M9") (pinfunction "VSS_M9") (pintype "power_in"))
      (node (ref "U1") (pin "P1") (pinfunction "VSS_P1") (pintype "power_in"))
      (node (ref "U1") (pin "P9") (pinfunction "VSS_P9") (pintype "power_in"))
      (node (ref "U1") (pin "T1") (pinfunction "VSS_T1") (pintype "power_in"))
      (node (ref "U1") (pin "T9") (pinfunction "VSS_T9") (pintype "power_in"))
      (node (ref "U2") (pin "11") (pinfunction "EP_11") (pintype "bidirectional"))
      (node (ref "U2") (pin "4") (pinfunction "PGND_4") (pintype "power_in"))
      (node (ref "U2") (pin "8") (pinfunction "GND_8") (pintype "power_in"))
      (node (ref "U3") (pin "A9") (pinfunction "VSS_A9") (pintype "power_in"))
      (node (ref "U3") (pin "B1") (pinfunction "VSSQ_B1") (pintype "power_in"))
      (node (ref "U3") (pin "B3") (pinfunction "VSS_B3") (pintype "power_in"))
      (node (ref "U3") (pin "B9") (pinfunction "VSSQ_B9") (pintype "power_in"))
      (node (ref "U3") (pin "D1") (pinfunction "VSSQ_D1") (pintype "power_in"))
      (node (ref "U3") (pin "D8") (pinfunction "VSSQ_D8") (pintype "power_in"))
      (node (ref "U3") (pin "E1") (pinfunction "VSS_E1") (pintype "power_in"))
      (node (ref "U3") (pin "E2") (pinfunction "VSSQ_E2") (pintype "power_in"))
      (node (ref "U3") (pin "E8") (pinfunction "VSSQ_E8") (pintype "power_in"))
      (node (ref "U3") (pin "F9") (pinfunction "VSSQ_F9") (pintype "power_in"))
      (node (ref "U3") (pin "G1") (pinfunction "VSSQ_G1") (pintype "power_in"))
      (node (ref "U3") (pin "G8") (pinfunction "VSS_G8") (pintype "power_in"))
      (node (ref "U3") (pin "G9") (pinfunction "VSSQ_G9") (pintype "power_in"))
      (node (ref "U3") (pin "J2") (pinfunction "VSS_J2") (pintype "power_in"))
      (node (ref "U3") (pin "J8") (pinfunction "VSS_J8") (pintype "power_in"))
      (node (ref "U3") (pin "M1") (pinfunction "VSS_M1") (pintype "power_in"))
      (node (ref "U3") (pin "M9") (pinfunction "VSS_M9") (pintype "power_in"))
      (node (ref "U3") (pin "P1") (pinfunction "VSS_P1") (pintype "power_in"))
      (node (ref "U3") (pin "P9") (pinfunction "VSS_P9") (pintype "power_in"))
      (node (ref "U3") (pin "T1") (pinfunction "VSS_T1") (pintype "power_in"))
      (node (ref "U3") (pin "T9") (pinfunction "VSS_T9") (pintype "power_in"))
    )
    (net (code "78") (name "Net-(U1A-ZQ)") (class "Default")
      (node (ref "R27") (pin "1") (pinfunction "1_1") (pintype "passive"))
      (node (ref "U1") (pin "L8") (pinfunction "ZQ_L8") (pintype "passive"))
    )
    (net (code "79") (name "Net-(U2-VLDOIN)") (class "Default")
      (node (ref "C1") (pin "2") (pinfunction "2_2") (pintype "passive"))
      (node (ref "R28") (pin "1") (pinfunction "1_1") (pintype "passive"))
      (node (ref "R29") (pin "2") (pinfunction "2_2") (pintype "passive"))
      (node (ref "U2") (pin "2") (pinfunction "VLDOIN_2") (pintype "passive"))
    )
    (net (code "80") (name "Net-(U3A-ZQ)") (class "Default")
      (node (ref "R30") (pin "1") (pinfunction "1_1") (pintype "passive"))
      (node (ref "U3") (pin "L8") (pinfunction "ZQ_L8") (pintype "passive"))
    )
    (net (code "81") (name "VCCO_DDR") (class "Default")
      (node (ref "C10") (pin "2") (pinfunction "2_2") (pintype "passive"))
      (node (ref "C11") (pin "2") (pinfunction "2_2") (pintype "passive"))
      (node (ref "C12") (pin "2") (pinfunction "2_2") (pintype "passive"))
      (node (ref "C13") (pin "2") (pinfunction "2_2") (pintype "passive"))
      (node (ref "C14") (pin "2") (pinfunction "2_2") (pintype "passive"))
      (node (ref "C15") (pin "2") (pinfunction "2_2") (pintype "passive"))
      (node (ref "C16") (pin "2") (pinfunction "2_2") (pintype "passive"))
      (node (ref "C17") (pin "2") (pinfunction "2_2") (pintype "passive"))
      (node (ref "C18") (pin "2") (pinfunction "2_2") (pintype "passive"))
      (node (ref "C19") (pin "2") (pinfunction "2_2") (pintype "passive"))
      (node (ref "C20") (pin "2") (pinfunction "2_2") (pintype "passive"))
      (node (ref "C21") (pin "2") (pinfunction "2_2") (pintype "passive"))
      (node (ref "C22") (pin "2") (pinfunction "2_2") (pintype "passive"))
      (node (ref "C23") (pin "2") (pinfunction "2_2") (pintype "passive"))
      (node (ref "C24") (pin "2") (pinfunction "2_2") (pintype "passive"))
      (node (ref "C25") (pin "2") (pinfunction "2_2") (pintype "passive"))
      (node (ref "C26") (pin "2") (pinfunction "2_2") (pintype "passive"))
      (node (ref "C27") (pin "2") (pinfunction "2_2") (pintype "passive"))
      (node (ref "C28") (pin "2") (pinfunction "2_2") (pintype "passive"))
      (node (ref "C3") (pin "2") (pinfunction "2_2") (pintype "passive"))
      (node (ref "C4") (pin "2") (pinfunction "2_2") (pintype "passive"))
      (node (ref "C9") (pin "2") (pinfunction "2_2") (pintype "passive"))
      (node (ref "R28") (pin "2") (pinfunction "2_2") (pintype "passive"))
      (node (ref "U1") (pin "A1") (pinfunction "VDDQ_A1") (pintype "power_in"))
      (node (ref "U1") (pin "A8") (pinfunction "VDDQ_A8") (pintype "power_in"))
      (node (ref "U1") (pin "B2") (pinfunction "VDD_B2") (pintype "power_in"))
      (node (ref "U1") (pin "C1") (pinfunction "VDDQ_C1") (pintype "power_in"))
      (node (ref "U1") (pin "C9") (pinfunction "VDDQ_C9") (pintype "power_in"))
      (node (ref "U1") (pin "D2") (pinfunction "VDDQ_D2") (pintype "power_in"))
      (node (ref "U1") (pin "D9") (pinfunction "VDD_D9") (pintype "power_in"))
      (node (ref "U1") (pin "E9") (pinfunction "VDDQ_E9") (pintype "power_in"))
      (node (ref "U1") (pin "F1") (pinfunction "VDDQ_F1") (pintype "power_in"))
      (node (ref "U1") (pin "G7") (pinfunction "VDD_G7") (pintype "power_in"))
      (node (ref "U1") (pin "H2") (pinfunction "VDDQ_H2") (pintype "power_in"))
      (node (ref "U1") (pin "H9") (pinfunction "VDDQ_H9") (pintype "power_in"))
      (node (ref "U1") (pin "K2") (pinfunction "VDD_K2") (pintype "power_in"))
      (node (ref "U1") (pin "K8") (pinfunction "VDD_K8") (pintype "power_in"))
      (node (ref "U1") (pin "N1") (pinfunction "VDD_N1") (pintype "power_in"))
      (node (ref "U1") (pin "N9") (pinfunction "VDD_N9") (pintype "power_in"))
      (node (ref "U1") (pin "R1") (pinfunction "VDD_R1") (pintype "power_in"))
      (node (ref "U1") (pin "R9") (pinfunction "VDD_R9") (pintype "power_in"))
      (node (ref "U2") (pin "1") (pinfunction "REFIN_1") (pintype "passive"))
      (node (ref "U3") (pin "A1") (pinfunction "VDDQ_A1") (pintype "power_in"))
      (node (ref "U3") (pin "A8") (pinfunction "VDDQ_A8") (pintype "power_in"))
      (node (ref "U3") (pin "B2") (pinfunction "VDD_B2") (pintype "power_in"))
      (node (ref "U3") (pin "C1") (pinfunction "VDDQ_C1") (pintype "power_in"))
      (node (ref "U3") (pin "C9") (pinfunction "VDDQ_C9") (pintype "power_in"))
      (node (ref "U3") (pin "D2") (pinfunction "VDDQ_D2") (pintype "power_in"))
      (node (ref "U3") (pin "D9") (pinfunction "VDD_D9") (pintype "power_in"))
      (node (ref "U3") (pin "E9") (pinfunction "VDDQ_E9") (pintype "power_in"))
      (node (ref "U3") (pin "F1") (pinfunction "VDDQ_F1") (pintype "power_in"))
      (node (ref "U3") (pin "G7") (pinfunction "VDD_G7") (pintype "power_in"))
      (node (ref "U3") (pin "H2") (pinfunction "VDDQ_H2") (pintype "power_in"))
      (node (ref "U3") (pin "H9") (pinfunction "VDDQ_H9") (pintype "power_in"))
      (node (ref "U3") (pin "K2") (pinfunction "VDD_K2") (pintype "power_in"))
      (node (ref "U3") (pin "K8") (pinfunction "VDD_K8") (pintype "power_in"))
      (node (ref "U3") (pin "N1") (pinfunction "VDD_N1") (pintype "power_in"))
      (node (ref "U3") (pin "N9") (pinfunction "VDD_N9") (pintype "power_in"))
      (node (ref "U3") (pin "R1") (pinfunction "VDD_R1") (pintype "power_in"))
      (node (ref "U3") (pin "R9") (pinfunction "VDD_R9") (pintype "power_in"))
    )
    (net (code "82") (name "VTT_DDR") (class "Default")
      (node (ref "C5") (pin "2") (pinfunction "2_2") (pintype "passive"))
      (node (ref "C6") (pin "2") (pinfunction "2_2") (pintype "passive"))
      (node (ref "C7") (pin "2") (pinfunction "2_2") (pintype "passive"))
      (node (ref "R10") (pin "2") (pinfunction "2_2") (pintype "passive"))
      (node (ref "R11") (pin "2") (pinfunction "2_2") (pintype "passive"))
      (node (ref "R12") (pin "2") (pinfunction "2_2") (pintype "passive"))
      (node (ref "R13") (pin "2") (pinfunction "2_2") (pintype "passive"))
      (node (ref "R14") (pin "2") (pinfunction "2_2") (pintype "passive"))
      (node (ref "R15") (pin "2") (pinfunction "2_2") (pintype "passive"))
      (node (ref "R16") (pin "2") (pinfunction "2_2") (pintype "passive"))
      (node (ref "R17") (pin "2") (pinfunction "2_2") (pintype "passive"))
      (node (ref "R18") (pin "2") (pinfunction "2_2") (pintype "passive"))
      (node (ref "R19") (pin "2") (pinfunction "2_2") (pintype "passive"))
      (node (ref "R20") (pin "2") (pinfunction "2_2") (pintype "passive"))
      (node (ref "R21") (pin "2") (pinfunction "2_2") (pintype "passive"))
      (node (ref "R22") (pin "2") (pinfunction "2_2") (pintype "passive"))
      (node (ref "R23") (pin "2") (pinfunction "2_2") (pintype "passive"))
      (node (ref "R24") (pin "2") (pinfunction "2_2") (pintype "passive"))
      (node (ref "R25") (pin "2") (pinfunction "2_2") (pintype "passive"))
      (node (ref "R26") (pin "2") (pinfunction "2_2") (pintype "passive"))
      (node (ref "R3") (pin "2") (pinfunction "2_2") (pintype "passive"))
      (node (ref "R4") (pin "2") (pinfunction "2_2") (pintype "passive"))
      (node (ref "R5") (pin "2") (pinfunction "2_2") (pintype "passive"))
      (node (ref "R6") (pin "2") (pinfunction "2_2") (pintype "passive"))
      (node (ref "R7") (pin "2") (pinfunction "2_2") (pintype "passive"))
      (node (ref "R8") (pin "2") (pinfunction "2_2") (pintype "passive"))
      (node (ref "R9") (pin "2") (pinfunction "2_2") (pintype "passive"))
      (node (ref "U2") (pin "3") (pinfunction "VO_3") (pintype "passive"))
      (node (ref "U2") (pin "5") (pinfunction "VOSNS_5") (pintype "passive"))
    )
    (net (code "83") (name "VTT_REF") (class "Default")
      (node (ref "C29") (pin "2") (pinfunction "2_2") (pintype "passive"))
      (node (ref "C30") (pin "2") (pinfunction "2_2") (pintype "passive"))
      (node (ref "C8") (pin "2") (pinfunction "2_2") (pintype "passive"))
      (node (ref "U1") (pin "H1") (pinfunction "VREFDQ_H1") (pintype "power_in"))
      (node (ref "U1") (pin "M8") (pinfunction "VREFCA_M8") (pintype "power_in"))
      (node (ref "U2") (pin "6") (pinfunction "REFOUT_6") (pintype "passive"))
      (node (ref "U3") (pin "H1") (pinfunction "VREFDQ_H1") (pintype "power_in"))
      (node (ref "U3") (pin "M8") (pinfunction "VREFCA_M8") (pintype "power_in"))
    )
    (net (code "84") (name "unconnected-(U1A-NC-PadJ1)") (class "Default")
      (node (ref "U1") (pin "J1") (pinfunction "NC_J1") (pintype "passive+no_connect"))
    )
    (net (code "85") (name "unconnected-(U1A-NC-PadJ9)") (class "Default")
      (node (ref "U1") (pin "J9") (pinfunction "NC_J9") (pintype "passive+no_connect"))
    )
    (net (code "86") (name "unconnected-(U1A-NC-PadL1)") (class "Default")
      (node (ref "U1") (pin "L1") (pinfunction "NC_L1") (pintype "passive+no_connect"))
    )
    (net (code "87") (name "unconnected-(U1A-NC-PadL9)") (class "Default")
      (node (ref "U1") (pin "L9") (pinfunction "NC_L9") (pintype "passive+no_connect"))
    )
    (net (code "88") (name "unconnected-(U1A-NC-PadM7)") (class "Default")
      (node (ref "U1") (pin "M7") (pinfunction "NC_M7") (pintype "passive+no_connect"))
    )
    (net (code "89") (name "unconnected-(U2-EN-Pad7)") (class "Default")
      (node (ref "U2") (pin "7") (pinfunction "EN_7") (pintype "input+no_connect"))
    )
    (net (code "90") (name "unconnected-(U2-PGOOD-Pad9)") (class "Default")
      (node (ref "U2") (pin "9") (pinfunction "PGOOD_9") (pintype "output+no_connect"))
    )
    (net (code "91") (name "unconnected-(U3A-NC-PadJ1)") (class "Default")
      (node (ref "U3") (pin "J1") (pinfunction "NC_J1") (pintype "passive+no_connect"))
    )
    (net (code "92") (name "unconnected-(U3A-NC-PadJ9)") (class "Default")
      (node (ref "U3") (pin "J9") (pinfunction "NC_J9") (pintype "passive+no_connect"))
    )
    (net (code "93") (name "unconnected-(U3A-NC-PadL1)") (class "Default")
      (node (ref "U3") (pin "L1") (pinfunction "NC_L1") (pintype "passive+no_connect"))
    )
    (net (code "94") (name "unconnected-(U3A-NC-PadL9)") (class "Default")
      (node (ref "U3") (pin "L9") (pinfunction "NC_L9") (pintype "passive+no_connect"))
    )
    (net (code "95") (name "unconnected-(U3A-NC-PadM7)") (class "Default")
      (node (ref "U3") (pin "M7") (pinfunction "NC_M7") (pintype "passive+no_connect"))
    )
  )
)
